# SCH_Power_Supply_SMPS_2023-06-14.net
KiCad netlist of a schematic drawn in EasyEDA
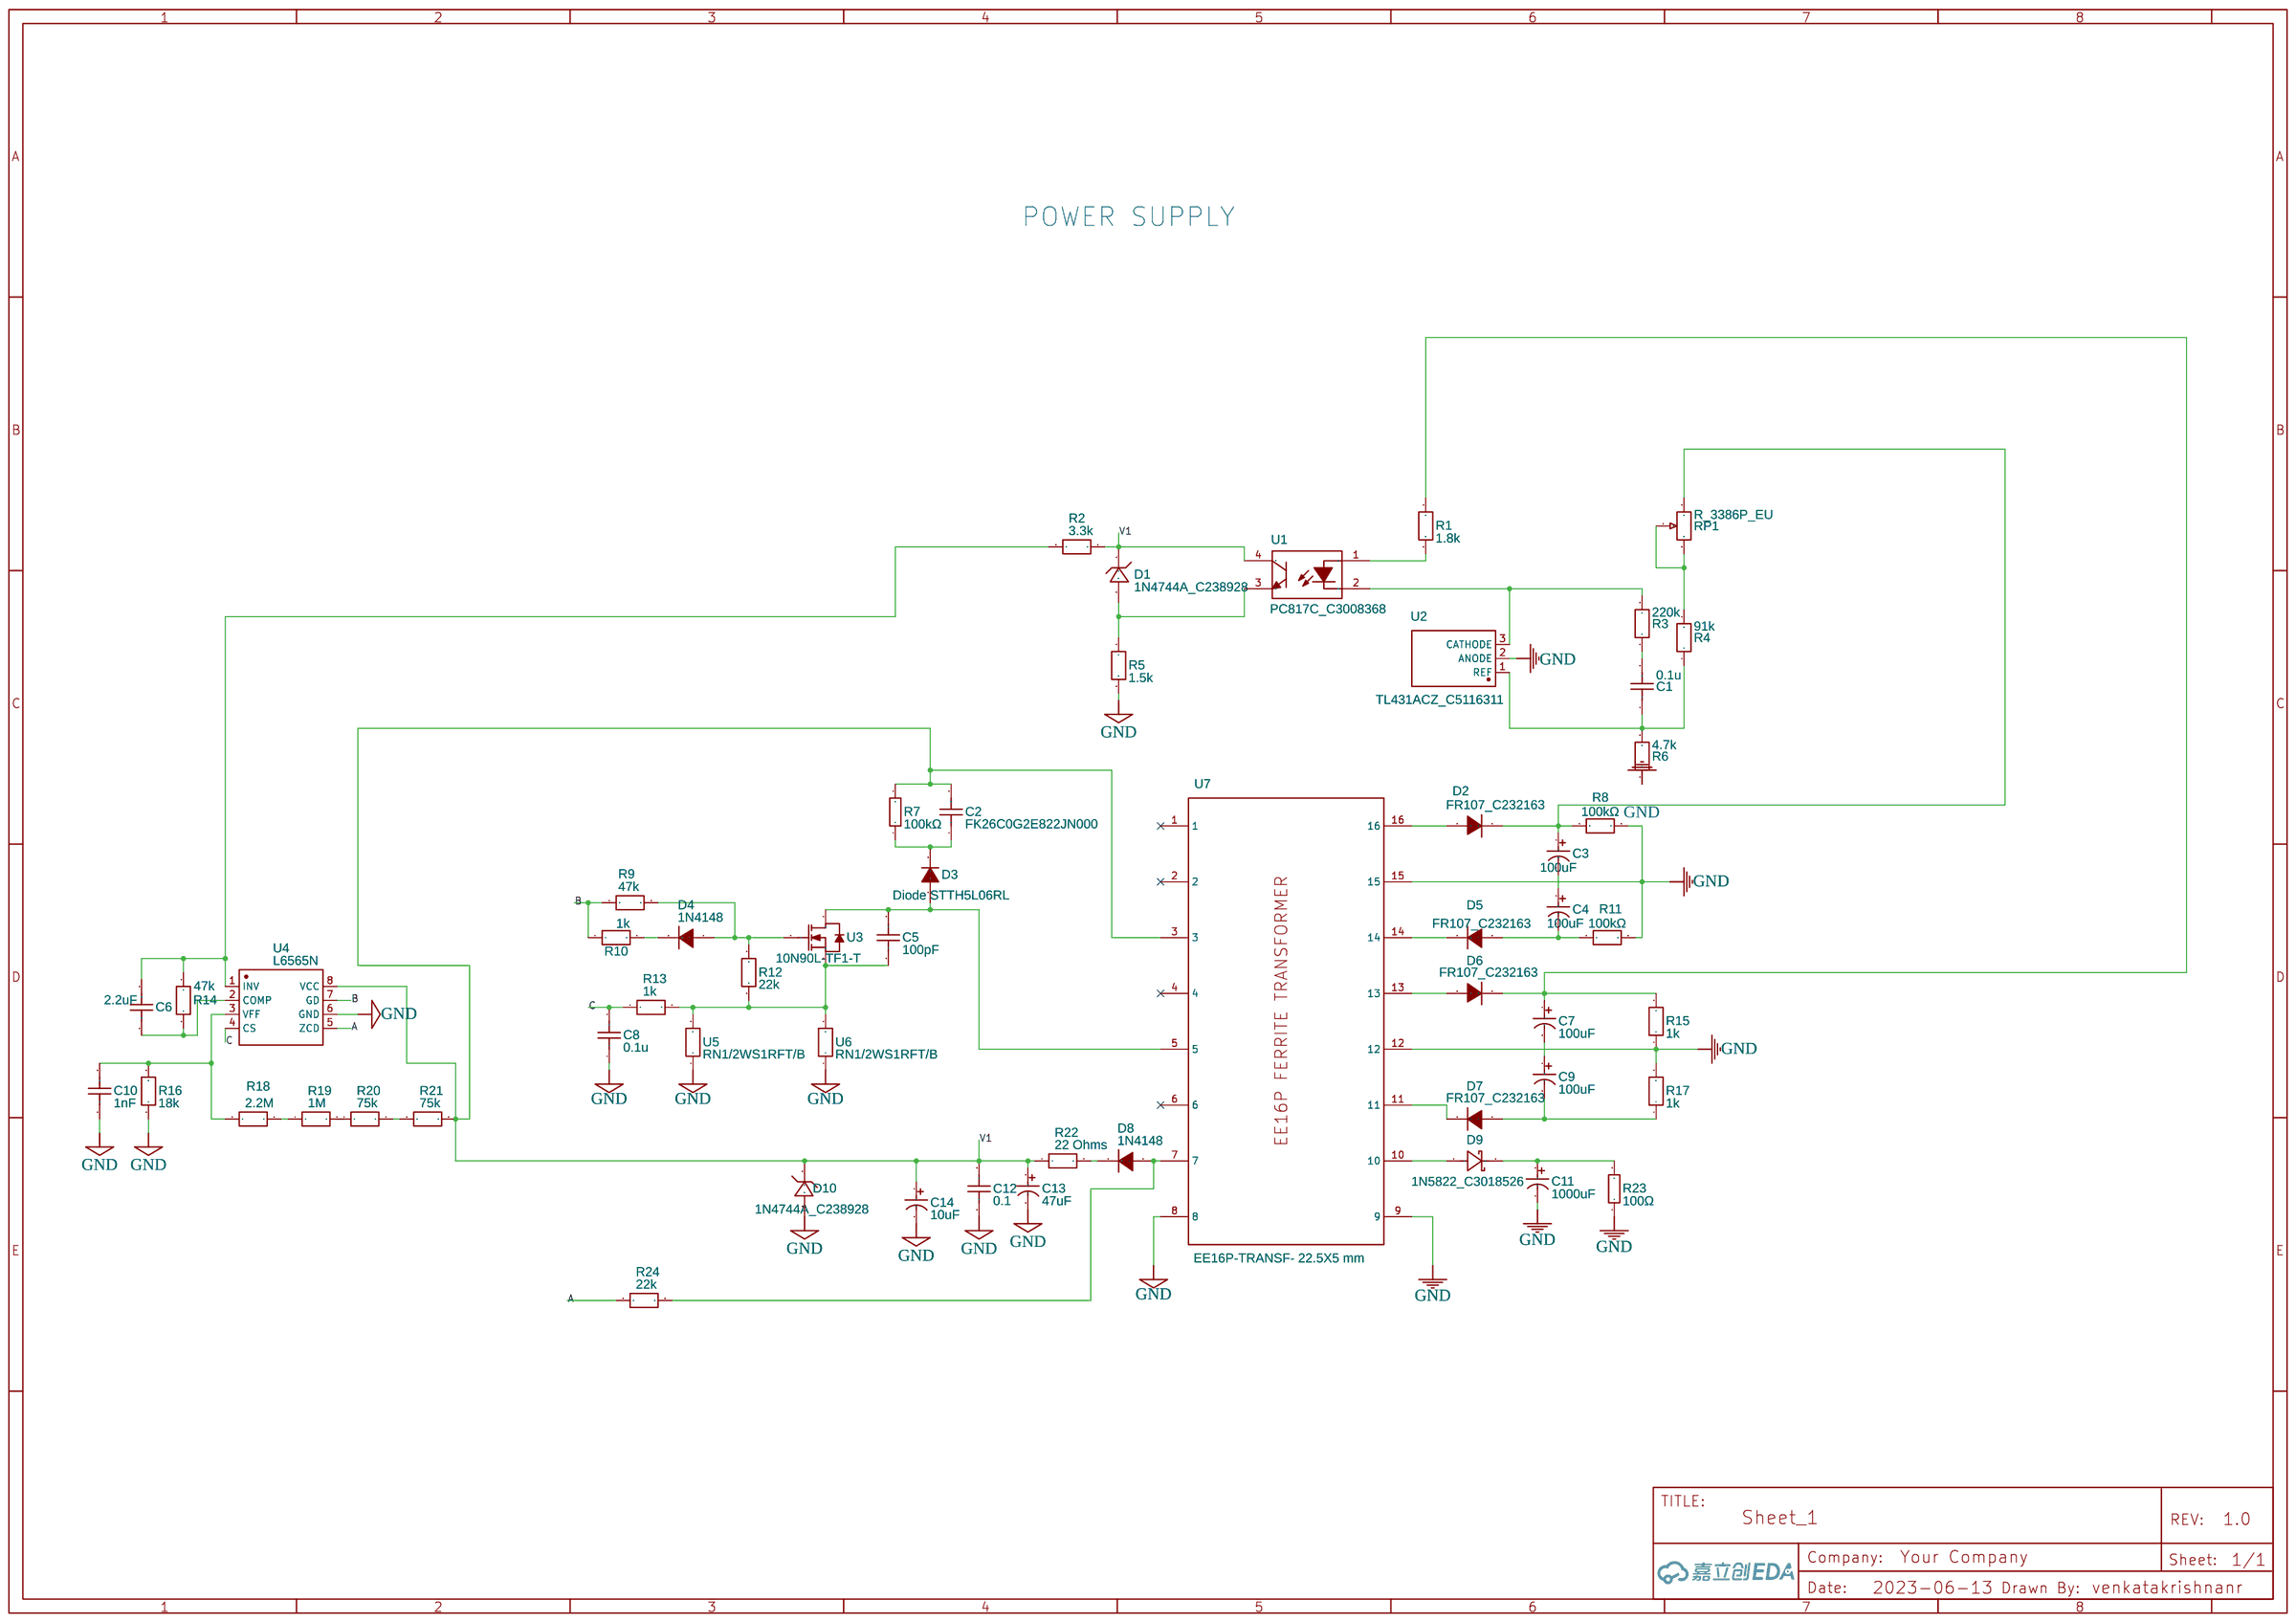
[diagram p0: schematic sheet]

(export (version "E")
  (design (tool "Eeschema 10.0.6"))
  (components
    (comp (ref "C1") (value "0.1u") (libsource (lib "") (part "C_0603_US_2")))
    (comp (ref "C2")
      (value "FK26C0G2E822JN000")
      (fields (field (name "BOM_Supplier Part") "C3691532"))
      (libsource (lib "") (part "FK26C0G2E822JN000"))
    )
    (comp (ref "C3")
      (value "100uF")
      (fields
        (field (name "BOM_Manufacturer Part") "ERS1KM101G16OT")
        (field (name "BOM_Supplier Part") "C106679")
      )
      (libsource (lib "") (part "ERS1KM101G16OT"))
    )
    (comp (ref "C4")
      (value "100uF")
      (fields
        (field (name "BOM_Manufacturer Part") "ERS1KM101G16OT")
        (field (name "BOM_Supplier Part") "C106679")
      )
      (libsource (lib "") (part "ERS1KM101G16OT"))
    )
    (comp (ref "C5")
      (value "100pF")
      (fields
        (field (name "BOM_Manufacturer Part") "CT81-N6Y5P1B101KSEW")
        (field (name "BOM_Supplier Part") "C278008")
      )
      (libsource (lib "") (part "CT81-N6Y5P1B101KSEW"))
    )
    (comp (ref "C6") (value "2.2uF") (libsource (lib "") (part "C_0603_US_1")))
    (comp (ref "C7")
      (value "100uF")
      (fields
        (field (name "BOM_Manufacturer Part") "ERS1VM101E12OT")
        (field (name "BOM_Supplier Part") "C106694")
      )
      (libsource (lib "") (part "ERS1VM101E12OT"))
    )
    (comp (ref "C8") (value "0.1u") (libsource (lib "") (part "C_0603_US")))
    (comp (ref "C9")
      (value "100uF")
      (fields
        (field (name "BOM_Manufacturer Part") "ERS1VM101E12OT")
        (field (name "BOM_Supplier Part") "C106694")
      )
      (libsource (lib "") (part "ERS1VM101E12OT"))
    )
    (comp (ref "C10") (value "1nF") (libsource (lib "") (part "C_0603_US")))
    (comp (ref "C11")
      (value "1000uF")
      (fields
        (field (name "BOM_Manufacturer Part") "KM108M016G16RR0VH2FP0")
        (field (name "BOM_Supplier Part") "C43909")
      )
      (libsource (lib "") (part "1000uF 16V"))
    )
    (comp (ref "C12") (value "0.1") (libsource (lib "") (part "C_0603_US")))
    (comp (ref "C13")
      (value "47uF")
      (fields
        (field (name "BOM_Manufacturer Part") "25YXF47MEFC5X11")
        (field (name "BOM_Supplier Part") "C88724")
      )
      (libsource (lib "") (part "25YXF47MEFC5X11"))
    )
    (comp (ref "C14")
      (value "10uF")
      (fields
        (field (name "BOM_Manufacturer Part") "KM106M025D11RR0VH2FP0")
        (field (name "BOM_Supplier Part") "C43347")
      )
      (libsource (lib "") (part "10uF 25V 5*11"))
    )
    (comp (ref "D1")
      (value "1N4744A_C238928")
      (fields (field (name "BOM_Manufacturer Part") "1N4744A") (field (name "BOM_Supplier Part") "C238928"))
      (libsource (lib "") (part "1N4744A_C238928"))
    )
    (comp (ref "D2")
      (value "FR107_C232163")
      (fields (field (name "BOM_Manufacturer Part") "FR107") (field (name "BOM_Supplier Part") "C232163"))
      (libsource (lib "") (part "FR107_C232163_1"))
    )
    (comp (ref "D3")
      (value "Diode STTH5L06RL")
      (fields
        (field (name "BOM_Manufacturer Part") "STMicroelectronics NV")
        (field (name "BOM_Supplier Part") "2353682")
      )
      (libsource (lib "") (part "Diode STTH5L06RL"))
    )
    (comp (ref "D4")
      (value "1N4148")
      (fields (field (name "BOM_Supplier Part") "C14516"))
      (libsource (lib "") (part "1N4148"))
    )
    (comp (ref "D5")
      (value "FR107_C232163")
      (fields (field (name "BOM_Manufacturer Part") "FR107") (field (name "BOM_Supplier Part") "C232163"))
      (libsource (lib "") (part "FR107_C232163"))
    )
    (comp (ref "D6")
      (value "FR107_C232163")
      (fields (field (name "BOM_Manufacturer Part") "FR107") (field (name "BOM_Supplier Part") "C232163"))
      (libsource (lib "") (part "FR107_C232163_1"))
    )
    (comp (ref "D7")
      (value "FR107_C232163")
      (fields (field (name "BOM_Manufacturer Part") "FR107") (field (name "BOM_Supplier Part") "C232163"))
      (libsource (lib "") (part "FR107_C232163"))
    )
    (comp (ref "D8")
      (value "1N4148")
      (fields (field (name "BOM_Supplier Part") "C14516"))
      (libsource (lib "") (part "1N4148"))
    )
    (comp (ref "D9")
      (value "1N5822_C3018526")
      (fields (field (name "BOM_Manufacturer Part") "1N5822") (field (name "BOM_Supplier Part") "C3018526"))
      (libsource (lib "") (part "1N5822_C3018526"))
    )
    (comp (ref "D10")
      (value "1N4744A_C238928")
      (fields (field (name "BOM_Manufacturer Part") "1N4744A") (field (name "BOM_Supplier Part") "C238928"))
      (libsource (lib "") (part "1N4744A_C238928_1"))
    )
    (comp (ref "R1") (value "1.8k") (libsource (lib "") (part "R_0603_EU")))
    (comp (ref "R2") (value "3.3k") (libsource (lib "") (part "R_0603_EU_3")))
    (comp (ref "R3") (value "220k") (libsource (lib "") (part "R_0603_EU_2")))
    (comp (ref "R4") (value "91k") (libsource (lib "") (part "R_0603_EU_2")))
    (comp (ref "R5") (value "1.5k") (libsource (lib "") (part "R_0603_EU")))
    (comp (ref "R6") (value "4.7k") (libsource (lib "") (part "R_0603_EU_2")))
    (comp (ref "R7")
      (value "100kΩ")
      (fields
        (field (name "BOM_Manufacturer Part") "MF1W-100KΩ±1% T")
        (field (name "BOM_Supplier Part") "C119512")
      )
      (libsource (lib "") (part "MF1W-100KΩ±1% T"))
    )
    (comp (ref "R8")
      (value "100kΩ")
      (fields
        (field (name "BOM_Manufacturer Part") "VR37000001003FA100")
        (field (name "BOM_Supplier Part") "C1365486")
      )
      (libsource (lib "") (part "VR37000001003FA100"))
    )
    (comp (ref "R9") (value "47k") (libsource (lib "") (part "R_0603_EU_1")))
    (comp (ref "R10") (value "1k") (libsource (lib "") (part "R_0603_EU_1")))
    (comp (ref "R11")
      (value "100kΩ")
      (fields
        (field (name "BOM_Manufacturer Part") "VR37000001003FA100")
        (field (name "BOM_Supplier Part") "C1365486")
      )
      (libsource (lib "") (part "VR37000001003FA100"))
    )
    (comp (ref "R12") (value "22k") (libsource (lib "") (part "R_0603_EU_2")))
    (comp (ref "R13") (value "1k") (libsource (lib "") (part "R_0603_EU_1")))
    (comp (ref "R14") (value "47k") (libsource (lib "") (part "R_0603_EU")))
    (comp (ref "R15") (value "1k") (libsource (lib "") (part "R_0603_EU_2")))
    (comp (ref "R16") (value "18k") (libsource (lib "") (part "R_0603_EU_2")))
    (comp (ref "R17") (value "1k") (libsource (lib "") (part "R_0603_EU_2")))
    (comp (ref "R18") (value "2.2M") (libsource (lib "") (part "R_0603_EU_1")))
    (comp (ref "R19") (value "1M") (libsource (lib "") (part "R_0603_EU_1")))
    (comp (ref "R20") (value "75k") (libsource (lib "") (part "R_0603_EU_1")))
    (comp (ref "R21") (value "75k") (libsource (lib "") (part "R_0603_EU_1")))
    (comp (ref "R22") (value "22 Ohms") (libsource (lib "") (part "R_0603_EU_1")))
    (comp (ref "R23")
      (value "100Ω")
      (fields
        (field (name "BOM_Manufacturer Part") "KNP1WS-100Ω±5%-XT52")
        (field (name "BOM_Supplier Part") "C479229")
      )
      (libsource (lib "") (part "KNP1WS-100Ω±5%-XT52"))
    )
    (comp (ref "R24") (value "22k") (libsource (lib "") (part "R_0603_EU_1")))
    (comp (ref "RP1") (value "R_3386P_EU") (libsource (lib "") (part "R_3386P_EU")))
    (comp (ref "U1")
      (value "PC817C_C3008368")
      (fields (field (name "BOM_Manufacturer Part") "PC817C") (field (name "BOM_Supplier Part") "C3008368"))
      (libsource (lib "") (part "PC817C_C3008368"))
    )
    (comp (ref "U2")
      (value "TL431ACZ_C5116311")
      (fields (field (name "BOM_Manufacturer Part") "TL431ACZ") (field (name "BOM_Supplier Part") "C5116311"))
      (libsource (lib "") (part "TL431ACZ_C5116311"))
    )
    (comp (ref "U3")
      (value "10N90L-TF1-T")
      (fields (field (name "BOM_Supplier Part") "C5310392"))
      (libsource (lib "") (part "10N90L-TF1-T"))
    )
    (comp (ref "U4")
      (value "L6565N")
      (fields (field (name "BOM_Supplier Part") "C31140"))
      (libsource (lib "") (part "L6565N"))
    )
    (comp (ref "U5")
      (value "RN1/2WS1RFT/B")
      (fields (field (name "BOM_Supplier Part") "C5200406"))
      (libsource (lib "") (part "RN1/2WS1RFT/B"))
    )
    (comp (ref "U6")
      (value "RN1/2WS1RFT/B")
      (fields (field (name "BOM_Supplier Part") "C5200406"))
      (libsource (lib "") (part "RN1/2WS1RFT/B"))
    )
    (comp (ref "U7")
      (value "EE16P-TRANSF- 22.5X5 mm")
      (fields (field (name "BOM_Supplier Part") "EE 16"))
      (libsource (lib "") (part "EE16P-TRANSF- 22.5X5 mm"))
    )
  )
  (nets
    (net (code "1") (name "/A") (class "Default")
      (node (ref "R24") (pin "1") (pinfunction "1_1") (pintype "unspecified"))
      (node (ref "U4") (pin "5") (pinfunction "ZCD_5") (pintype "unspecified"))
    )
    (net (code "2") (name "/B") (class "Default")
      (node (ref "R10") (pin "1") (pinfunction "1_1") (pintype "unspecified"))
      (node (ref "R9") (pin "1") (pinfunction "1_1") (pintype "unspecified"))
      (node (ref "U4") (pin "7") (pinfunction "GD_7") (pintype "unspecified"))
    )
    (net (code "3") (name "/C") (class "Default")
      (node (ref "C8") (pin "2") (pinfunction "2_2") (pintype "unspecified"))
      (node (ref "R13") (pin "1") (pinfunction "1_1") (pintype "unspecified"))
      (node (ref "U4") (pin "4") (pinfunction "CS_4") (pintype "unspecified"))
    )
    (net (code "4") (name "/V1") (class "Default")
      (node (ref "C12") (pin "2") (pinfunction "2_2") (pintype "unspecified"))
      (node (ref "C13") (pin "1") (pinfunction "1_1") (pintype "input"))
      (node (ref "C14") (pin "1") (pinfunction "1_1") (pintype "input"))
      (node (ref "C2") (pin "2") (pinfunction "2_2") (pintype "unspecified"))
      (node (ref "D1") (pin "1") (pinfunction "1_1") (pintype "unspecified"))
      (node (ref "D10") (pin "1") (pinfunction "1_1") (pintype "unspecified"))
      (node (ref "R2") (pin "1") (pinfunction "1_1") (pintype "unspecified"))
      (node (ref "R21") (pin "2") (pinfunction "2_2") (pintype "unspecified"))
      (node (ref "R22") (pin "1") (pinfunction "1_1") (pintype "unspecified"))
      (node (ref "R7") (pin "2") (pinfunction "2_2") (pintype "unspecified"))
      (node (ref "U1") (pin "4") (pinfunction "COL_4") (pintype "unspecified"))
      (node (ref "U4") (pin "8") (pinfunction "VCC_8") (pintype "unspecified"))
      (node (ref "U7") (pin "3") (pinfunction "3_3") (pintype "unspecified"))
    )
    (net (code "5") (name "GND") (class "Default")
      (node (ref "C10") (pin "1") (pinfunction "1_1") (pintype "unspecified"))
      (node (ref "C11") (pin "2") (pinfunction "2_2") (pintype "input"))
      (node (ref "C12") (pin "1") (pinfunction "1_1") (pintype "unspecified"))
      (node (ref "C13") (pin "2") (pinfunction "2_2") (pintype "input"))
      (node (ref "C14") (pin "2") (pinfunction "2_2") (pintype "input"))
      (node (ref "C8") (pin "1") (pinfunction "1_1") (pintype "unspecified"))
      (node (ref "D10") (pin "2") (pinfunction "2_2") (pintype "unspecified"))
      (node (ref "R11") (pin "2") (pinfunction "2_2") (pintype "unspecified"))
      (node (ref "R15") (pin "1") (pinfunction "1_1") (pintype "unspecified"))
      (node (ref "R16") (pin "1") (pinfunction "1_1") (pintype "unspecified"))
      (node (ref "R17") (pin "2") (pinfunction "2_2") (pintype "unspecified"))
      (node (ref "R23") (pin "1") (pinfunction "1_1") (pintype "unspecified"))
      (node (ref "R5") (pin "2") (pinfunction "2_2") (pintype "unspecified"))
      (node (ref "R6") (pin "1") (pinfunction "1_1") (pintype "unspecified"))
      (node (ref "R8") (pin "2") (pinfunction "2_2") (pintype "unspecified"))
      (node (ref "U2") (pin "2") (pinfunction "ANODE_2") (pintype "unspecified"))
      (node (ref "U4") (pin "6") (pinfunction "GND_6") (pintype "unspecified"))
      (node (ref "U5") (pin "1") (pinfunction "1_1") (pintype "unspecified"))
      (node (ref "U6") (pin "1") (pinfunction "1_1") (pintype "unspecified"))
      (node (ref "U7") (pin "12") (pinfunction "12_12") (pintype "unspecified"))
      (node (ref "U7") (pin "15") (pinfunction "15_15") (pintype "unspecified"))
      (node (ref "U7") (pin "8") (pinfunction "8_8") (pintype "unspecified"))
      (node (ref "U7") (pin "9") (pinfunction "9_9") (pintype "unspecified"))
    )
    (net (code "6") (name "Net-(C1-Pad2)") (class "Default")
      (node (ref "C1") (pin "2") (pinfunction "2_2") (pintype "unspecified"))
      (node (ref "R3") (pin "1") (pinfunction "1_1") (pintype "unspecified"))
    )
    (net (code "7") (name "Net-(C3-Pad2)") (class "Default")
      (node (ref "C3") (pin "2") (pinfunction "2_2") (pintype "input"))
      (node (ref "C4") (pin "1") (pinfunction "1_1") (pintype "input"))
    )
    (net (code "8") (name "Net-(C7-Pad2)") (class "Default")
      (node (ref "C7") (pin "2") (pinfunction "2_2") (pintype "input"))
      (node (ref "C9") (pin "1") (pinfunction "1_1") (pintype "input"))
    )
    (net (code "9") (name "Net-(D2-A)") (class "Default")
      (node (ref "D2") (pin "2") (pinfunction "A_2") (pintype "unspecified"))
      (node (ref "U7") (pin "16") (pinfunction "16_16") (pintype "unspecified"))
    )
    (net (code "10") (name "Net-(D2-C)") (class "Default")
      (node (ref "C3") (pin "1") (pinfunction "1_1") (pintype "input"))
      (node (ref "D2") (pin "1") (pinfunction "C_1") (pintype "unspecified"))
      (node (ref "R8") (pin "1") (pinfunction "1_1") (pintype "unspecified"))
      (node (ref "RP1") (pin "1") (pinfunction "1_1") (pintype "input"))
    )
    (net (code "11") (name "Net-(D3-A)") (class "Default")
      (node (ref "C5") (pin "2") (pinfunction "2_2") (pintype "unspecified"))
      (node (ref "D3") (pin "1") (pinfunction "A_1") (pintype "unspecified"))
      (node (ref "U3") (pin "2") (pinfunction "D_2") (pintype "unspecified"))
      (node (ref "U7") (pin "5") (pinfunction "5_5") (pintype "unspecified"))
    )
    (net (code "12") (name "Net-(D3-K)") (class "Default")
      (node (ref "C2") (pin "1") (pinfunction "1_1") (pintype "unspecified"))
      (node (ref "D3") (pin "2") (pinfunction "K_2") (pintype "unspecified"))
      (node (ref "R7") (pin "1") (pinfunction "1_1") (pintype "unspecified"))
    )
    (net (code "13") (name "Net-(D4-A)") (class "Default")
      (node (ref "D4") (pin "1") (pinfunction "A_1") (pintype "unspecified"))
      (node (ref "R12") (pin "2") (pinfunction "2_2") (pintype "unspecified"))
      (node (ref "R9") (pin "2") (pinfunction "2_2") (pintype "unspecified"))
      (node (ref "U3") (pin "1") (pinfunction "G_1") (pintype "unspecified"))
    )
    (net (code "14") (name "Net-(D4-C)") (class "Default")
      (node (ref "D4") (pin "2") (pinfunction "C_2") (pintype "unspecified"))
      (node (ref "R10") (pin "2") (pinfunction "2_2") (pintype "unspecified"))
    )
    (net (code "15") (name "Net-(D5-A)") (class "Default")
      (node (ref "C4") (pin "2") (pinfunction "2_2") (pintype "input"))
      (node (ref "D5") (pin "2") (pinfunction "A_2") (pintype "unspecified"))
      (node (ref "R11") (pin "1") (pinfunction "1_1") (pintype "unspecified"))
    )
    (net (code "16") (name "Net-(D5-C)") (class "Default")
      (node (ref "D5") (pin "1") (pinfunction "C_1") (pintype "unspecified"))
      (node (ref "U7") (pin "14") (pinfunction "14_14") (pintype "unspecified"))
    )
    (net (code "17") (name "Net-(D6-A)") (class "Default")
      (node (ref "D6") (pin "2") (pinfunction "A_2") (pintype "unspecified"))
      (node (ref "U7") (pin "13") (pinfunction "13_13") (pintype "unspecified"))
    )
    (net (code "18") (name "Net-(D6-C)") (class "Default")
      (node (ref "C7") (pin "1") (pinfunction "1_1") (pintype "input"))
      (node (ref "D6") (pin "1") (pinfunction "C_1") (pintype "unspecified"))
      (node (ref "R1") (pin "1") (pinfunction "1_1") (pintype "unspecified"))
      (node (ref "R15") (pin "2") (pinfunction "2_2") (pintype "unspecified"))
    )
    (net (code "19") (name "Net-(D7-A)") (class "Default")
      (node (ref "C9") (pin "2") (pinfunction "2_2") (pintype "input"))
      (node (ref "D7") (pin "2") (pinfunction "A_2") (pintype "unspecified"))
      (node (ref "R17") (pin "1") (pinfunction "1_1") (pintype "unspecified"))
    )
    (net (code "20") (name "Net-(D7-C)") (class "Default")
      (node (ref "D7") (pin "1") (pinfunction "C_1") (pintype "unspecified"))
      (node (ref "U7") (pin "11") (pinfunction "11_11") (pintype "unspecified"))
    )
    (net (code "21") (name "Net-(D8-A)") (class "Default")
      (node (ref "D8") (pin "1") (pinfunction "A_1") (pintype "unspecified"))
      (node (ref "R24") (pin "2") (pinfunction "2_2") (pintype "unspecified"))
      (node (ref "U7") (pin "7") (pinfunction "7_7") (pintype "unspecified"))
    )
    (net (code "22") (name "Net-(D8-C)") (class "Default")
      (node (ref "D8") (pin "2") (pinfunction "C_2") (pintype "unspecified"))
      (node (ref "R22") (pin "2") (pinfunction "2_2") (pintype "unspecified"))
    )
    (net (code "23") (name "Net-(D9-A)") (class "Default")
      (node (ref "D9") (pin "1") (pinfunction "A_1") (pintype "unspecified"))
      (node (ref "U7") (pin "10") (pinfunction "10_10") (pintype "unspecified"))
    )
    (net (code "24") (name "Net-(D9-K)") (class "Default")
      (node (ref "C11") (pin "1") (pinfunction "1_1") (pintype "input"))
      (node (ref "D9") (pin "2") (pinfunction "K_2") (pintype "unspecified"))
      (node (ref "R23") (pin "2") (pinfunction "2_2") (pintype "unspecified"))
    )
    (net (code "25") (name "Net-(R4-Pad2)") (class "Default")
      (node (ref "R4") (pin "2") (pinfunction "2_2") (pintype "unspecified"))
      (node (ref "RP1") (pin "2") (pinfunction "2_2") (pintype "input"))
      (node (ref "RP1") (pin "3") (pinfunction "3_3") (pintype "input"))
    )
    (net (code "26") (name "Net-(R18-Pad2)") (class "Default")
      (node (ref "R18") (pin "2") (pinfunction "2_2") (pintype "unspecified"))
      (node (ref "R19") (pin "1") (pinfunction "1_1") (pintype "unspecified"))
    )
    (net (code "27") (name "Net-(R19-Pad2)") (class "Default")
      (node (ref "R19") (pin "2") (pinfunction "2_2") (pintype "unspecified"))
      (node (ref "R20") (pin "1") (pinfunction "1_1") (pintype "unspecified"))
    )
    (net (code "28") (name "Net-(R20-Pad2)") (class "Default")
      (node (ref "R20") (pin "2") (pinfunction "2_2") (pintype "unspecified"))
      (node (ref "R21") (pin "1") (pinfunction "1_1") (pintype "unspecified"))
    )
    (net (code "29") (name "Net-(U1-AN)") (class "Default")
      (node (ref "R1") (pin "2") (pinfunction "2_2") (pintype "unspecified"))
      (node (ref "U1") (pin "1") (pinfunction "AN_1") (pintype "unspecified"))
    )
    (net (code "30") (name "Net-(U1-CAT)") (class "Default")
      (node (ref "R3") (pin "2") (pinfunction "2_2") (pintype "unspecified"))
      (node (ref "U1") (pin "2") (pinfunction "CAT_2") (pintype "unspecified"))
      (node (ref "U2") (pin "3") (pinfunction "CATHODE_3") (pintype "unspecified"))
    )
    (net (code "31") (name "Net-(U1-EM)") (class "Default")
      (node (ref "D1") (pin "2") (pinfunction "2_2") (pintype "unspecified"))
      (node (ref "R5") (pin "1") (pinfunction "1_1") (pintype "unspecified"))
      (node (ref "U1") (pin "3") (pinfunction "EM_3") (pintype "unspecified"))
    )
    (net (code "32") (name "Net-(U2-REF)") (class "Default")
      (node (ref "C1") (pin "1") (pinfunction "1_1") (pintype "unspecified"))
      (node (ref "R4") (pin "1") (pinfunction "1_1") (pintype "unspecified"))
      (node (ref "R6") (pin "2") (pinfunction "2_2") (pintype "unspecified"))
      (node (ref "U2") (pin "1") (pinfunction "REF_1") (pintype "unspecified"))
    )
    (net (code "33") (name "Net-(U3-S)") (class "Default")
      (node (ref "C5") (pin "1") (pinfunction "1_1") (pintype "unspecified"))
      (node (ref "R12") (pin "1") (pinfunction "1_1") (pintype "unspecified"))
      (node (ref "R13") (pin "2") (pinfunction "2_2") (pintype "unspecified"))
      (node (ref "U3") (pin "3") (pinfunction "S_3") (pintype "unspecified"))
      (node (ref "U5") (pin "2") (pinfunction "2_2") (pintype "unspecified"))
      (node (ref "U6") (pin "2") (pinfunction "2_2") (pintype "unspecified"))
    )
    (net (code "34") (name "Net-(U4-COMP)") (class "Default")
      (node (ref "C6") (pin "2") (pinfunction "2_2") (pintype "unspecified"))
      (node (ref "R14") (pin "2") (pinfunction "2_2") (pintype "unspecified"))
      (node (ref "U4") (pin "2") (pinfunction "COMP_2") (pintype "unspecified"))
    )
    (net (code "35") (name "Net-(U4-INV)") (class "Default")
      (node (ref "C6") (pin "1") (pinfunction "1_1") (pintype "unspecified"))
      (node (ref "R14") (pin "1") (pinfunction "1_1") (pintype "unspecified"))
      (node (ref "R2") (pin "2") (pinfunction "2_2") (pintype "unspecified"))
      (node (ref "U4") (pin "1") (pinfunction "INV_1") (pintype "unspecified"))
    )
    (net (code "36") (name "Net-(U4-VFF)") (class "Default")
      (node (ref "C10") (pin "2") (pinfunction "2_2") (pintype "unspecified"))
      (node (ref "R16") (pin "2") (pinfunction "2_2") (pintype "unspecified"))
      (node (ref "R18") (pin "1") (pinfunction "1_1") (pintype "unspecified"))
      (node (ref "U4") (pin "3") (pinfunction "VFF_3") (pintype "unspecified"))
    )
    (net (code "37") (name "unconnected-(U7-Pad1)") (class "Default")
      (node (ref "U7") (pin "1") (pinfunction "1_1") (pintype "unspecified+no_connect"))
    )
    (net (code "38") (name "unconnected-(U7-Pad2)") (class "Default")
      (node (ref "U7") (pin "2") (pinfunction "2_2") (pintype "unspecified+no_connect"))
    )
    (net (code "39") (name "unconnected-(U7-Pad4)") (class "Default")
      (node (ref "U7") (pin "4") (pinfunction "4_4") (pintype "unspecified+no_connect"))
    )
    (net (code "40") (name "unconnected-(U7-Pad6)") (class "Default")
      (node (ref "U7") (pin "6") (pinfunction "6_6") (pintype "unspecified+no_connect"))
    )
  )
)
